# MCU_RF.net
KiCad netlist of a schematic drawn in Altium Designer
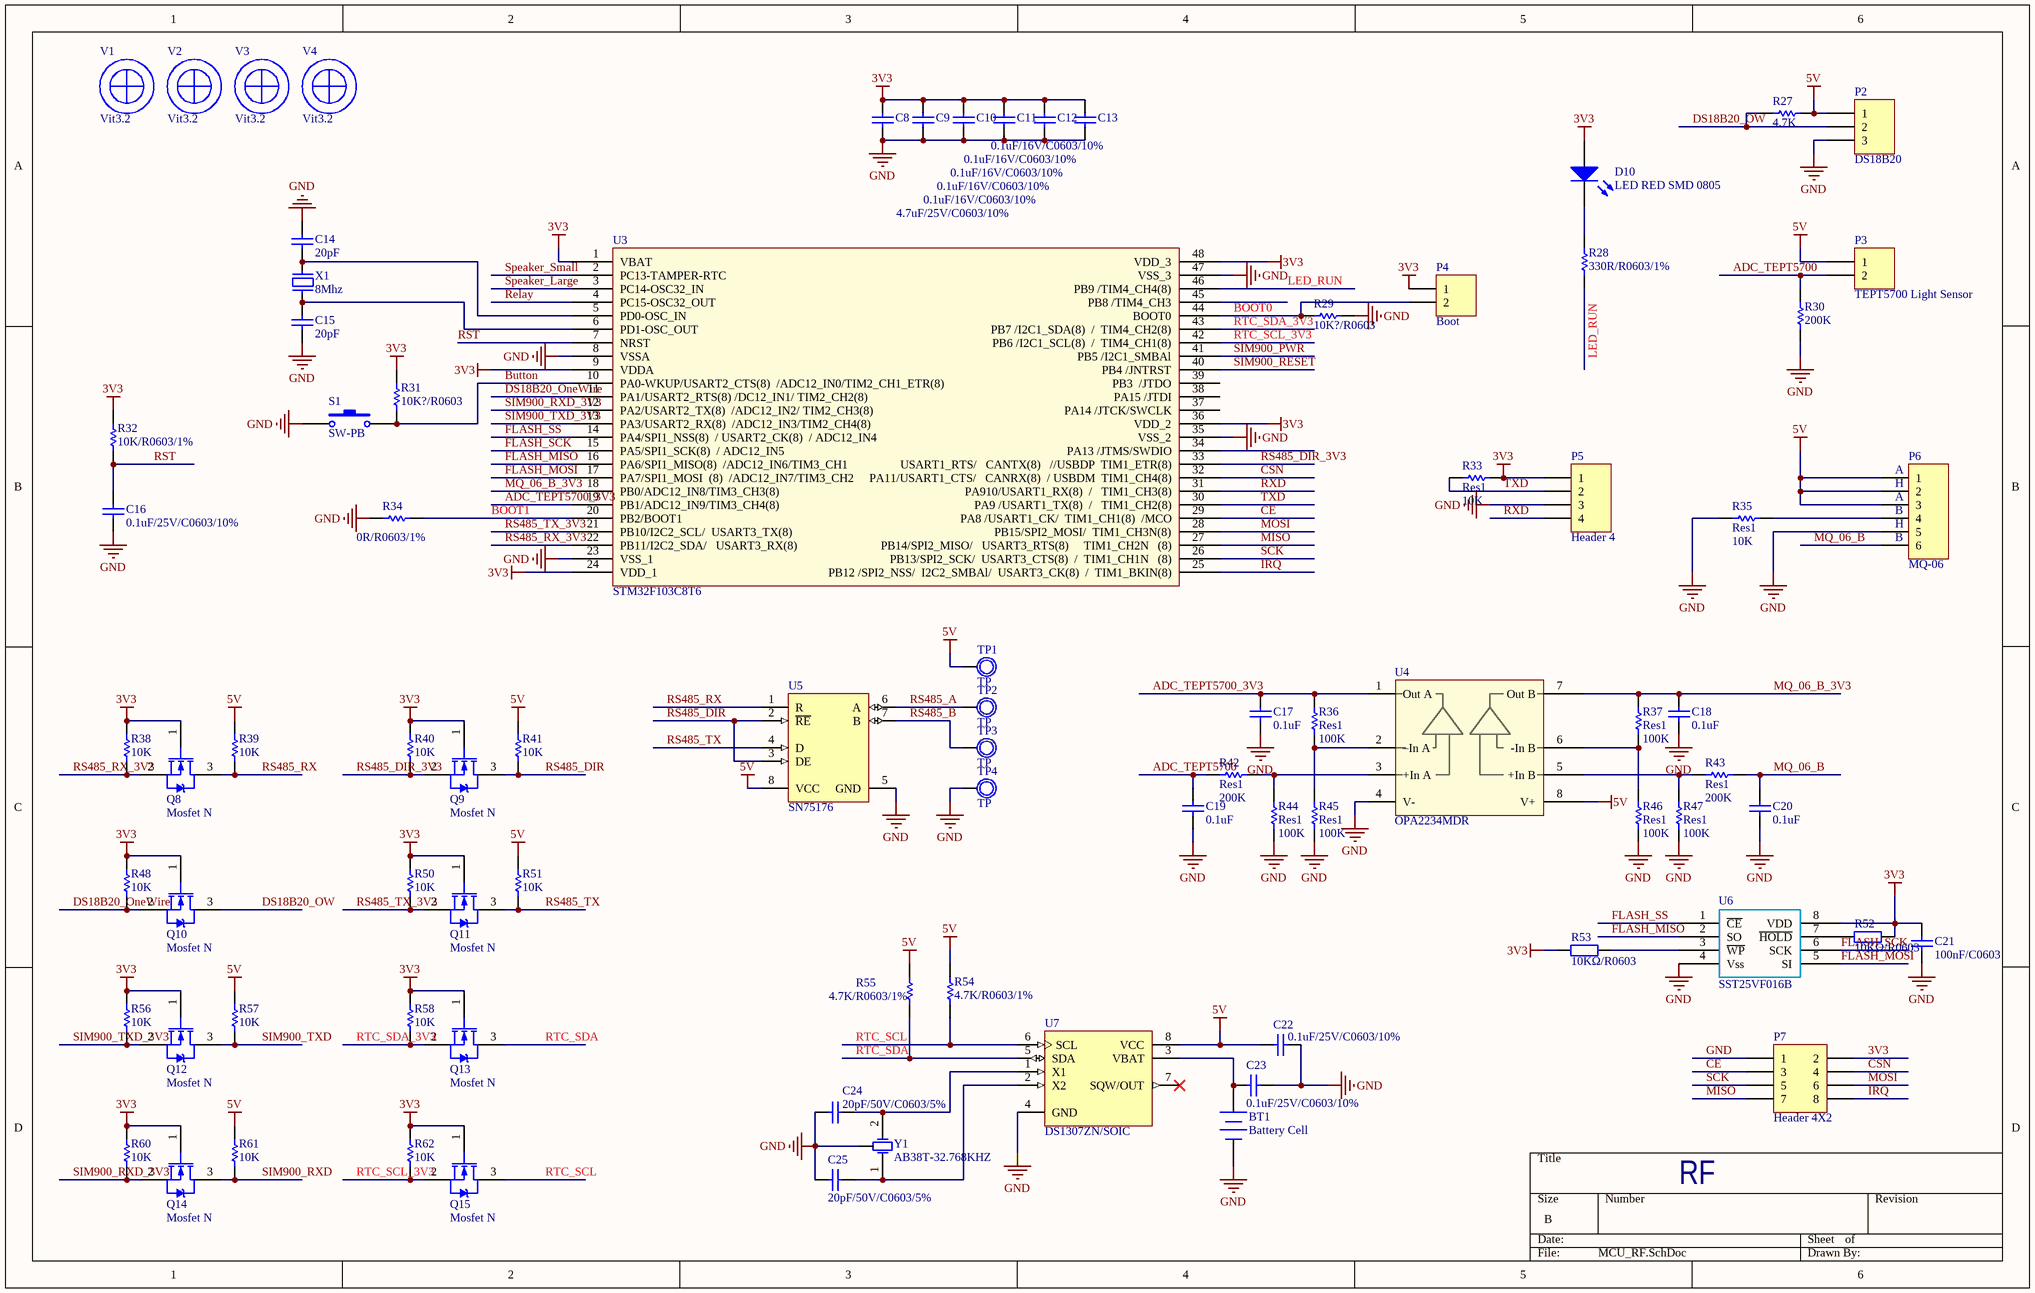
[diagram p0: MCU_RF.SchDoc]

(export (version "E")
  (design (tool "Eeschema 10.0.6"))
  (components
    (comp (ref "BT1")
      (value "Battery Cell")
      (footprint "Tuyens Library for Altium Designer:Battery CELL_HOLDER")
      (description "HOLDER COINCELL 2032 RETAINRCLIP")
      (fields
        (field (name "MANUFACTURER") "MPD (Memory Protection Devices)")
        (field (name "MANUFACTURER PART NUMBER") "BS-7")
      )
      (libsource (lib "Manh_Miscellaneous") (part "Battery Holder Cell 20mm"))
    )
    (comp (ref "C8")
      (value "4.7uF/25V/C0603/10%")
      (footprint "Tuyens Library for Altium Designer:C0603")
      (description "CAP CER 4.7UF 25V 10% X6S 0603")
      (fields
        (field (name "MANUFACTURER") "Murata Electronics North America")
        (field (name "MANUFACTURER PART NUMBER") "GRM188C81E475KE11D")
      )
      (libsource (lib "Manh_Capacitor") (part "4.7uF/25V/C0603/10%"))
    )
    (comp (ref "C9")
      (value "0.1uF/16V/C0603/10%")
      (footprint "Tuyens Library for Altium Designer:C0603")
      (description "CAP CER 0.1UF 16V 10% X7R 0603")
      (fields
        (field (name "MANUFACTURER") "Kemet")
        (field (name "MANUFACTURER PART NUMBER") "C0603C104K4RACTU")
      )
      (libsource (lib "Manh_Capacitor") (part "0.1uF/16V/C0603/10%"))
    )
    (comp (ref "C10")
      (value "0.1uF/16V/C0603/10%")
      (footprint "Tuyens Library for Altium Designer:C0603")
      (description "CAP CER 0.1UF 16V 10% X7R 0603")
      (fields
        (field (name "MANUFACTURER") "Kemet")
        (field (name "MANUFACTURER PART NUMBER") "C0603C104K4RACTU")
      )
      (libsource (lib "Manh_Capacitor") (part "0.1uF/16V/C0603/10%"))
    )
    (comp (ref "C11")
      (value "0.1uF/16V/C0603/10%")
      (footprint "Tuyens Library for Altium Designer:C0603")
      (description "CAP CER 0.1UF 16V 10% X7R 0603")
      (fields
        (field (name "MANUFACTURER") "Kemet")
        (field (name "MANUFACTURER PART NUMBER") "C0603C104K4RACTU")
      )
      (libsource (lib "Manh_Capacitor") (part "0.1uF/16V/C0603/10%"))
    )
    (comp (ref "C12")
      (value "0.1uF/16V/C0603/10%")
      (footprint "Tuyens Library for Altium Designer:C0603")
      (description "CAP CER 0.1UF 16V 10% X7R 0603")
      (fields
        (field (name "MANUFACTURER") "Kemet")
        (field (name "MANUFACTURER PART NUMBER") "C0603C104K4RACTU")
      )
      (libsource (lib "Manh_Capacitor") (part "0.1uF/16V/C0603/10%"))
    )
    (comp (ref "C13")
      (value "0.1uF/16V/C0603/10%")
      (footprint "Tuyens Library for Altium Designer:C0603")
      (description "CAP CER 0.1UF 16V 10% X7R 0603")
      (fields
        (field (name "MANUFACTURER") "Kemet")
        (field (name "MANUFACTURER PART NUMBER") "C0603C104K4RACTU")
      )
      (libsource (lib "Manh_Capacitor") (part "0.1uF/16V/C0603/10%"))
    )
    (comp (ref "C14")
      (value "20pF")
      (footprint "C0603")
      (description "Capacitor")
      (libsource (lib "Miscellaneous Devices") (part "Cap"))
    )
    (comp (ref "C15")
      (value "20pF")
      (footprint "C0603")
      (description "Capacitor")
      (libsource (lib "Miscellaneous Devices") (part "Cap"))
    )
    (comp (ref "C16")
      (value "0.1uF/25V/C0603/10%")
      (footprint "Tuyens Library for Altium Designer:C0603")
      (description "CAP CER 0.1UF 25V 10% X7R 0603")
      (fields
        (field (name "MANUFACTURER") "Murata Electronics North America")
        (field (name "MANUFACTURER PART NUMBER") "GRM188R71E104KA01D")
      )
      (libsource (lib "Manh_Capacitor") (part "0.1uF/25V/C0603/10%"))
    )
    (comp (ref "C17")
      (value "0.1uF")
      (footprint "Tuyens Library for Altium Designer:C0603")
      (description "CAP CER 0.1UF 25V 10% X7R 0603")
      (fields
        (field (name "MANUFACTURER") "Murata Electronics North America")
        (field (name "MANUFACTURER PART NUMBER") "GRM188R71E104KA01D")
      )
      (libsource (lib "Manh_Capacitor") (part "0.1uF/25V/C0603/10%"))
    )
    (comp (ref "C18")
      (value "0.1uF")
      (footprint "Tuyens Library for Altium Designer:C0603")
      (description "CAP CER 0.1UF 25V 10% X7R 0603")
      (fields
        (field (name "MANUFACTURER") "Murata Electronics North America")
        (field (name "MANUFACTURER PART NUMBER") "GRM188R71E104KA01D")
      )
      (libsource (lib "Manh_Capacitor") (part "0.1uF/25V/C0603/10%"))
    )
    (comp (ref "C19")
      (value "0.1uF")
      (footprint "Tuyens Library for Altium Designer:C0603")
      (description "CAP CER 0.1UF 25V 10% X7R 0603")
      (fields
        (field (name "MANUFACTURER") "Murata Electronics North America")
        (field (name "MANUFACTURER PART NUMBER") "GRM188R71E104KA01D")
      )
      (libsource (lib "Manh_Capacitor") (part "0.1uF/25V/C0603/10%"))
    )
    (comp (ref "C20")
      (value "0.1uF")
      (footprint "Tuyens Library for Altium Designer:C0603")
      (description "CAP CER 0.1UF 25V 10% X7R 0603")
      (fields
        (field (name "MANUFACTURER") "Murata Electronics North America")
        (field (name "MANUFACTURER PART NUMBER") "GRM188R71E104KA01D")
      )
      (libsource (lib "Manh_Capacitor") (part "0.1uF/25V/C0603/10%"))
    )
    (comp (ref "C21")
      (value "100nF/C0603")
      (footprint "c0603")
      (description "Capacitor")
      (fields (field (name "PUBLISHER") "Altium Limited"))
      (libsource (lib "Miscellaneous Devices") (part "Cap"))
    )
    (comp (ref "C22")
      (value "0.1uF/25V/C0603/10%")
      (footprint "Tuyens Library for Altium Designer:C0603")
      (description "CAP CER 0.1UF 25V 10% X7R 0603")
      (fields
        (field (name "MANUFACTURER") "Murata Electronics North America")
        (field (name "MANUFACTURER PART NUMBER") "GRM188R71E104KA01D")
      )
      (libsource (lib "Manh_Capacitor") (part "0.1uF/25V/C0603/10%"))
    )
    (comp (ref "C23")
      (value "0.1uF/25V/C0603/10%")
      (footprint "Tuyens Library for Altium Designer:C0603")
      (description "CAP CER 0.1UF 25V 10% X7R 0603")
      (fields
        (field (name "MANUFACTURER") "Murata Electronics North America")
        (field (name "MANUFACTURER PART NUMBER") "GRM188R71E104KA01D")
      )
      (libsource (lib "Manh_Capacitor") (part "0.1uF/25V/C0603/10%"))
    )
    (comp (ref "C24")
      (value "20pF/50V/C0603/5%")
      (footprint "Tuyens Library for Altium Designer:C0603")
      (description "CAP CER 20PF 50V 5% NP0 0603")
      (fields
        (field (name "MANUFACTURER") "Samsung Electro-Mechanics America, Inc.")
        (field (name "MANUFACTURER PART NUMBER") "CL10C200JB8NNNC")
      )
      (libsource (lib "Manh_Capacitor") (part "20pF/50V/C0603/5%"))
    )
    (comp (ref "C25")
      (value "20pF/50V/C0603/5%")
      (footprint "Tuyens Library for Altium Designer:C0603")
      (description "CAP CER 20PF 50V 5% NP0 0603")
      (fields
        (field (name "MANUFACTURER") "Samsung Electro-Mechanics America, Inc.")
        (field (name "MANUFACTURER PART NUMBER") "CL10C200JB8NNNC")
      )
      (libsource (lib "Manh_Capacitor") (part "20pF/50V/C0603/5%"))
    )
    (comp (ref "D10")
      (value "LED RED SMD 0805")
      (footprint "Tuyens Library for Altium Designer:led0805")
      (description "LED RED DIFFUSED 0805 SMD")
      (fields
        (field (name "MANUFACTURER") "OSRAM Opto Semiconductors Inc.")
        (field (name "MANUFACTURER PART NUMBER") "LH R974-LP-1")
      )
      (libsource (lib "Manh_LED") (part "LED RED SMD 0805"))
    )
    (comp (ref "P2")
      (value "DS18B20")
      (footprint "HDR1X3")
      (description "Header, 3-Pin")
      (fields (field (name "PUBLISHER") "Altium Limited"))
      (libsource (lib "Miscellaneous Connectors") (part "Header 3"))
    )
    (comp (ref "P3")
      (value "TEPT5700 Light Sensor")
      (footprint "LED-5-BLUE")
      (description "Header, 2-Pin")
      (fields (field (name "PUBLISHER") "Altium Limited"))
      (libsource (lib "Miscellaneous Connectors") (part "Header 2"))
    )
    (comp (ref "P4")
      (value "Boot")
      (footprint "HDR1X2")
      (description "Header, 2-Pin")
      (fields (field (name "PUBLISHER") "Altium Limited"))
      (libsource (lib "Miscellaneous Connectors") (part "Header 2"))
    )
    (comp (ref "P5")
      (value "Header 4")
      (footprint "HDR1X4")
      (description "Header, 4-Pin")
      (fields (field (name "PUBLISHER") "Altium Limited"))
      (libsource (lib "Miscellaneous Connectors") (part "Header 4"))
    )
    (comp (ref "P6")
      (value "MQ-06")
      (footprint "MQ-02")
      (description "Header, 6-Pin")
      (fields (field (name "PUBLISHER") "Altium Limited"))
      (libsource (lib "Miscellaneous Connectors") (part "Header 6"))
    )
    (comp (ref "P7")
      (value "Header 4X2")
      (footprint "HDR2X4")
      (description "Header, 4-Pin, Dual row")
      (fields (field (name "PUBLISHER") "Altium Limited"))
      (libsource (lib "Miscellaneous Connectors") (part "Header 4X2"))
    )
    (comp (ref "Q8")
      (value "Mosfet N")
      (footprint "SOT 23")
      (libsource (lib "Tuyens Library for Altium Designer") (part "Mosfet N"))
    )
    (comp (ref "Q9")
      (value "Mosfet N")
      (footprint "SOT 23")
      (libsource (lib "Tuyens Library for Altium Designer") (part "Mosfet N"))
    )
    (comp (ref "Q10")
      (value "Mosfet N")
      (footprint "SOT 23")
      (libsource (lib "Tuyens Library for Altium Designer") (part "Mosfet N"))
    )
    (comp (ref "Q11")
      (value "Mosfet N")
      (footprint "SOT 23")
      (libsource (lib "Tuyens Library for Altium Designer") (part "Mosfet N"))
    )
    (comp (ref "Q12")
      (value "Mosfet N")
      (footprint "SOT 23")
      (libsource (lib "Tuyens Library for Altium Designer") (part "Mosfet N"))
    )
    (comp (ref "Q13")
      (value "Mosfet N")
      (footprint "SOT 23")
      (libsource (lib "Tuyens Library for Altium Designer") (part "Mosfet N"))
    )
    (comp (ref "Q14")
      (value "Mosfet N")
      (footprint "SOT 23")
      (libsource (lib "Tuyens Library for Altium Designer") (part "Mosfet N"))
    )
    (comp (ref "Q15")
      (value "Mosfet N")
      (footprint "SOT 23")
      (libsource (lib "Tuyens Library for Altium Designer") (part "Mosfet N"))
    )
    (comp (ref "R27")
      (value "4.7K")
      (footprint "SM-RES-0805")
      (description "Resistor")
      (fields (field (name "Comment") "Res1") (field (name "PUBLISHER") "Altium Limited"))
      (libsource (lib "Miscellaneous Devices") (part "Res1"))
    )
    (comp (ref "R28")
      (value "330R/R0603/1%")
      (footprint "Tuyens Library for Altium Designer:R0603")
      (description "RES SMD 330 OHM 1% 1/10W 0603")
      (fields
        (field (name "MANUFACTURER") "Yageo")
        (field (name "MANUFACTURER PART NUMBER") "RC0603FR-07330RL")
      )
      (libsource (lib "Manh_Resistor") (part "330R/R0603/1%"))
    )
    (comp (ref "R29")
      (value "10K?/R0603")
      (footprint "R0603")
      (description "Resistor")
      (libsource (lib "Miscellaneous Devices") (part "Res1"))
    )
    (comp (ref "R30")
      (value "200K")
      (footprint "SM-RES-0805")
      (description "Resistor")
      (fields (field (name "Comment") "Res1") (field (name "PUBLISHER") "Altium Limited"))
      (libsource (lib "Miscellaneous Devices") (part "Res1"))
    )
    (comp (ref "R31")
      (value "10K?/R0603")
      (footprint "R0603")
      (description "Resistor")
      (libsource (lib "Miscellaneous Devices") (part "Res1"))
    )
    (comp (ref "R32")
      (value "10K/R0603/1%")
      (footprint "Tuyens Library for Altium Designer:R0603")
      (description "RES SMD 10M OHM 1% 1/10W 0603")
      (fields
        (field (name "MANUFACTURER") "Yageo")
        (field (name "MANUFACTURER PART NUMBER") "RC0603FR-0710ML")
      )
      (libsource (lib "Manh_Resistor") (part "10M/R0603/1%"))
    )
    (comp (ref "R33")
      (value "Res1")
      (footprint "R0603")
      (description "Resistor")
      (fields (field (name "ALTIUM_VALUE") "10K") (field (name "PUBLISHER") "Altium Limited"))
      (libsource (lib "Miscellaneous Devices") (part "Res1"))
    )
    (comp (ref "R34")
      (value "0R/R0603/1%")
      (footprint "Tuyens Library for Altium Designer:R0603")
      (description "RES SMD 0.01 OHM 1% 1/10W 0603")
      (fields
        (field (name "MANUFACTURER") "Yageo")
        (field (name "MANUFACTURER PART NUMBER") "RL0603FR-070R01L")
      )
      (libsource (lib "Manh_Resistor") (part "0R/R0603/1%"))
    )
    (comp (ref "R35")
      (value "Res1")
      (footprint "SM-RES-0805")
      (description "Resistor")
      (fields (field (name "ALTIUM_VALUE") "10K") (field (name "PUBLISHER") "Altium Limited"))
      (libsource (lib "Miscellaneous Devices") (part "Res1"))
    )
    (comp (ref "R36")
      (value "Res1")
      (footprint "R0603")
      (description "Resistor")
      (fields (field (name "ALTIUM_VALUE") "100K") (field (name "PUBLISHER") "Altium Limited"))
      (libsource (lib "Miscellaneous Devices") (part "Res1"))
    )
    (comp (ref "R37")
      (value "Res1")
      (footprint "R0603")
      (description "Resistor")
      (fields (field (name "ALTIUM_VALUE") "100K") (field (name "PUBLISHER") "Altium Limited"))
      (libsource (lib "Miscellaneous Devices") (part "Res1"))
    )
    (comp (ref "R38")
      (value "10K")
      (footprint "Tuyens Library for Altium Designer:R0603")
      (description "RES SMD 4.7K OHM 1% 1/10W 0603")
      (fields
        (field (name "MANUFACTURER") "Yageo")
        (field (name "MANUFACTURER PART NUMBER") "RC0603FR-074K7L")
      )
      (libsource (lib "Manh_Resistor") (part "4.7K/R0603/1%"))
    )
    (comp (ref "R39")
      (value "10K")
      (footprint "Tuyens Library for Altium Designer:R0603")
      (description "RES SMD 4.7K OHM 1% 1/10W 0603")
      (fields
        (field (name "MANUFACTURER") "Yageo")
        (field (name "MANUFACTURER PART NUMBER") "RC0603FR-074K7L")
      )
      (libsource (lib "Manh_Resistor") (part "4.7K/R0603/1%"))
    )
    (comp (ref "R40")
      (value "10K")
      (footprint "Tuyens Library for Altium Designer:R0603")
      (description "RES SMD 4.7K OHM 1% 1/10W 0603")
      (fields
        (field (name "MANUFACTURER") "Yageo")
        (field (name "MANUFACTURER PART NUMBER") "RC0603FR-074K7L")
      )
      (libsource (lib "Manh_Resistor") (part "4.7K/R0603/1%"))
    )
    (comp (ref "R41")
      (value "10K")
      (footprint "Tuyens Library for Altium Designer:R0603")
      (description "RES SMD 4.7K OHM 1% 1/10W 0603")
      (fields
        (field (name "MANUFACTURER") "Yageo")
        (field (name "MANUFACTURER PART NUMBER") "RC0603FR-074K7L")
      )
      (libsource (lib "Manh_Resistor") (part "4.7K/R0603/1%"))
    )
    (comp (ref "R42")
      (value "Res1")
      (footprint "R0603")
      (description "Resistor")
      (fields (field (name "ALTIUM_VALUE") "200K") (field (name "PUBLISHER") "Altium Limited"))
      (libsource (lib "Miscellaneous Devices") (part "Res1"))
    )
    (comp (ref "R43")
      (value "Res1")
      (footprint "R0603")
      (description "Resistor")
      (fields (field (name "ALTIUM_VALUE") "200K") (field (name "PUBLISHER") "Altium Limited"))
      (libsource (lib "Miscellaneous Devices") (part "Res1"))
    )
    (comp (ref "R44")
      (value "Res1")
      (footprint "R0603")
      (description "Resistor")
      (fields (field (name "ALTIUM_VALUE") "100K") (field (name "PUBLISHER") "Altium Limited"))
      (libsource (lib "Miscellaneous Devices") (part "Res1"))
    )
    (comp (ref "R45")
      (value "Res1")
      (footprint "R0603")
      (description "Resistor")
      (fields (field (name "ALTIUM_VALUE") "100K") (field (name "PUBLISHER") "Altium Limited"))
      (libsource (lib "Miscellaneous Devices") (part "Res1"))
    )
    (comp (ref "R46")
      (value "Res1")
      (footprint "R0603")
      (description "Resistor")
      (fields (field (name "ALTIUM_VALUE") "100K") (field (name "PUBLISHER") "Altium Limited"))
      (libsource (lib "Miscellaneous Devices") (part "Res1"))
    )
    (comp (ref "R47")
      (value "Res1")
      (footprint "R0603")
      (description "Resistor")
      (fields (field (name "ALTIUM_VALUE") "100K") (field (name "PUBLISHER") "Altium Limited"))
      (libsource (lib "Miscellaneous Devices") (part "Res1"))
    )
    (comp (ref "R48")
      (value "10K")
      (footprint "Tuyens Library for Altium Designer:R0603")
      (description "RES SMD 4.7K OHM 1% 1/10W 0603")
      (fields
        (field (name "MANUFACTURER") "Yageo")
        (field (name "MANUFACTURER PART NUMBER") "RC0603FR-074K7L")
      )
      (libsource (lib "Manh_Resistor") (part "4.7K/R0603/1%"))
    )
    (comp (ref "R50")
      (value "10K")
      (footprint "Tuyens Library for Altium Designer:R0603")
      (description "RES SMD 4.7K OHM 1% 1/10W 0603")
      (fields
        (field (name "MANUFACTURER") "Yageo")
        (field (name "MANUFACTURER PART NUMBER") "RC0603FR-074K7L")
      )
      (libsource (lib "Manh_Resistor") (part "4.7K/R0603/1%"))
    )
    (comp (ref "R51")
      (value "10K")
      (footprint "Tuyens Library for Altium Designer:R0603")
      (description "RES SMD 4.7K OHM 1% 1/10W 0603")
      (fields
        (field (name "MANUFACTURER") "Yageo")
        (field (name "MANUFACTURER PART NUMBER") "RC0603FR-074K7L")
      )
      (libsource (lib "Manh_Resistor") (part "4.7K/R0603/1%"))
    )
    (comp (ref "R52")
      (value "10KΩ/R0603")
      (footprint "r0603")
      (description "Resistor")
      (libsource (lib "Miscellaneous Devices") (part "Res2"))
    )
    (comp (ref "R53")
      (value "10KΩ/R0603")
      (footprint "r0603")
      (description "Resistor")
      (libsource (lib "Miscellaneous Devices") (part "Res2"))
    )
    (comp (ref "R54")
      (value "4.7K/R0603/1%")
      (footprint "Tuyens Library for Altium Designer:R0603")
      (description "RES SMD 4.7K OHM 1% 1/10W 0603")
      (fields
        (field (name "MANUFACTURER") "Yageo")
        (field (name "MANUFACTURER PART NUMBER") "RC0603FR-074K7L")
      )
      (libsource (lib "Manh_Resistor") (part "4.7K/R0603/1%"))
    )
    (comp (ref "R55")
      (value "4.7K/R0603/1%")
      (footprint "Tuyens Library for Altium Designer:R0603")
      (description "RES SMD 4.7K OHM 1% 1/10W 0603")
      (fields
        (field (name "MANUFACTURER") "Yageo")
        (field (name "MANUFACTURER PART NUMBER") "RC0603FR-074K7L")
      )
      (libsource (lib "Manh_Resistor") (part "4.7K/R0603/1%"))
    )
    (comp (ref "R56")
      (value "10K")
      (footprint "Tuyens Library for Altium Designer:R0603")
      (description "RES SMD 4.7K OHM 1% 1/10W 0603")
      (fields
        (field (name "MANUFACTURER") "Yageo")
        (field (name "MANUFACTURER PART NUMBER") "RC0603FR-074K7L")
      )
      (libsource (lib "Manh_Resistor") (part "4.7K/R0603/1%"))
    )
    (comp (ref "R57")
      (value "10K")
      (footprint "Tuyens Library for Altium Designer:R0603")
      (description "RES SMD 4.7K OHM 1% 1/10W 0603")
      (fields
        (field (name "MANUFACTURER") "Yageo")
        (field (name "MANUFACTURER PART NUMBER") "RC0603FR-074K7L")
      )
      (libsource (lib "Manh_Resistor") (part "4.7K/R0603/1%"))
    )
    (comp (ref "R58")
      (value "10K")
      (footprint "Tuyens Library for Altium Designer:R0603")
      (description "RES SMD 4.7K OHM 1% 1/10W 0603")
      (fields
        (field (name "MANUFACTURER") "Yageo")
        (field (name "MANUFACTURER PART NUMBER") "RC0603FR-074K7L")
      )
      (libsource (lib "Manh_Resistor") (part "4.7K/R0603/1%"))
    )
    (comp (ref "R60")
      (value "10K")
      (footprint "Tuyens Library for Altium Designer:R0603")
      (description "RES SMD 4.7K OHM 1% 1/10W 0603")
      (fields
        (field (name "MANUFACTURER") "Yageo")
        (field (name "MANUFACTURER PART NUMBER") "RC0603FR-074K7L")
      )
      (libsource (lib "Manh_Resistor") (part "4.7K/R0603/1%"))
    )
    (comp (ref "R61")
      (value "10K")
      (footprint "Tuyens Library for Altium Designer:R0603")
      (description "RES SMD 4.7K OHM 1% 1/10W 0603")
      (fields
        (field (name "MANUFACTURER") "Yageo")
        (field (name "MANUFACTURER PART NUMBER") "RC0603FR-074K7L")
      )
      (libsource (lib "Manh_Resistor") (part "4.7K/R0603/1%"))
    )
    (comp (ref "R62")
      (value "10K")
      (footprint "Tuyens Library for Altium Designer:R0603")
      (description "RES SMD 4.7K OHM 1% 1/10W 0603")
      (fields
        (field (name "MANUFACTURER") "Yageo")
        (field (name "MANUFACTURER PART NUMBER") "RC0603FR-074K7L")
      )
      (libsource (lib "Manh_Resistor") (part "4.7K/R0603/1%"))
    )
    (comp (ref "S1")
      (value "SW-PB")
      (footprint "Button-2pin")
      (description "Switch")
      (fields (field (name "PUBLISHER") "Altium Limited"))
      (libsource (lib "Tuyens Library for Altium Designer") (part "SW-PB"))
    )
    (comp (ref "TP1")
      (value "TP")
      (footprint "TP1")
      (description "Test Point")
      (libsource (lib "syhaunguyen") (part "TP1"))
    )
    (comp (ref "TP2")
      (value "TP")
      (footprint "TP1")
      (description "Test Point")
      (libsource (lib "syhaunguyen") (part "TP1"))
    )
    (comp (ref "TP3")
      (value "TP")
      (footprint "TP1")
      (description "Test Point")
      (libsource (lib "syhaunguyen") (part "TP1"))
    )
    (comp (ref "TP4")
      (value "TP")
      (footprint "TP1")
      (description "Test Point")
      (libsource (lib "syhaunguyen") (part "TP1"))
    )
    (comp (ref "U3")
      (value "STM32F103C8T6")
      (footprint "ST_TSQFP50P910X910X160-48N")
      (libsource (lib "Tuyens Library for Altium Designer") (part "STM32F103C8T6"))
    )
    (comp (ref "U4")
      (value "OPA2234MDR")
      (footprint "SOP 8Pin")
      (description "LOW-POWER, PRECISION  SINGLE-SUPPLY OPERATIONAL AMPLIFIERS")
      (libsource (lib "Tuyens Library for Altium Designer") (part "OPA2234M"))
    )
    (comp (ref "U5")
      (value "SN75176")
      (footprint "SOP127P600X175-8N")
      (description "RS485 Interface")
      (libsource (lib "tqk") (part "SN75176_RS485"))
    )
    (comp (ref "U6")
      (value "SST25VF016B")
      (footprint "SOIC8")
      (libsource (lib "Tuyen's Library for Altium Designer") (part "SST25VF016B"))
    )
    (comp (ref "U7")
      (value "DS1307ZN/SOIC")
      (footprint "Tuyens Library for Altium Designer:SOIC-8")
      (description "IC RTC CLK/CALENDAR I2C 8-SOIC")
      (fields
        (field (name "MANUFACTURER") "Maxim Integrated")
        (field (name "MANUFACTURER PART NUMBER") "DS1307ZN+T&R")
      )
      (libsource (lib "Manh_MCU") (part "DS1307ZN+T&R"))
    )
    (comp (ref "V1")
      (value "Vit3.2")
      (footprint "Vit3.2")
      (libsource (lib "Tuyens Library for Altium Designer") (part "Vit3.2"))
    )
    (comp (ref "V2")
      (value "Vit3.2")
      (footprint "Vit3.2")
      (libsource (lib "Tuyens Library for Altium Designer") (part "Vit3.2"))
    )
    (comp (ref "V3")
      (value "Vit3.2")
      (footprint "Vit3.2")
      (libsource (lib "Tuyens Library for Altium Designer") (part "Vit3.2"))
    )
    (comp (ref "V4")
      (value "Vit3.2")
      (footprint "Vit3.2")
      (libsource (lib "Tuyens Library for Altium Designer") (part "Vit3.2"))
    )
    (comp (ref "X1")
      (value "8Mhz")
      (footprint "XT2")
      (description "Crystal For all Crystal 2pin.")
      (libsource (lib "syhaunguyen") (part "XT2"))
    )
    (comp (ref "Y1")
      (value "AB38T-32.768KHZ")
      (footprint "Tuyens Library for Altium Designer:ZTA - 38k")
      (description "CRYSTAL 32.7680KHZ 12.5PF T/H")
      (fields (field (name "MANUFACTURER") "Abracon LLC"))
      (libsource (lib "Manh_Crystal") (part "AB38T-32.768KHZ"))
    )
  )
  (nets
    (net (code "1") (name "/ADC_TEPT5700") (class "Default")
      (node (ref "C19") (pin "1") (pinfunction "1_1") (pintype "passive"))
      (node (ref "P3") (pin "2") (pinfunction "2_2") (pintype "passive"))
      (node (ref "R30") (pin "2") (pinfunction "2_2") (pintype "passive"))
      (node (ref "R42") (pin "1") (pinfunction "1_1") (pintype "passive"))
    )
    (net (code "2") (name "/ADC_TEPT5700_3V3") (class "Default")
      (node (ref "C17") (pin "1") (pinfunction "1_1") (pintype "passive"))
      (node (ref "R36") (pin "2") (pinfunction "2_2") (pintype "passive"))
      (node (ref "U3") (pin "19") (pinfunction "PB1/ADC12_IN9/TIM3_CH4(8)_19") (pintype "passive"))
      (node (ref "U4") (pin "1") (pinfunction "Out_A_1") (pintype "passive"))
    )
    (net (code "3") (name "/BOOT0") (class "Default")
      (node (ref "P4") (pin "2") (pinfunction "2_2") (pintype "passive"))
      (node (ref "R29") (pin "2") (pinfunction "2_2") (pintype "passive"))
      (node (ref "U3") (pin "44") (pinfunction "BOOT0_44") (pintype "passive"))
    )
    (net (code "4") (name "/BOOT1") (class "Default")
      (node (ref "R34") (pin "2") (pinfunction "2_2") (pintype "passive"))
      (node (ref "U3") (pin "20") (pinfunction "PB2/BOOT1_20") (pintype "passive"))
    )
    (net (code "5") (name "/Button") (class "Default")
      (node (ref "R31") (pin "2") (pinfunction "2_2") (pintype "passive"))
      (node (ref "S1") (pin "2") (pinfunction "2_2") (pintype "passive"))
      (node (ref "U3") (pin "10") (pinfunction "PA0-WKUP/USART2_CTS(8)__/ADC12_IN0/TIM2_CH1_ETR(8)_10") (pintype "passive"))
    )
    (net (code "6") (name "/CE") (class "Default")
      (node (ref "P7") (pin "3") (pinfunction "3_3") (pintype "passive"))
      (node (ref "U3") (pin "29") (pinfunction "PA8_/USART1_CK/__TIM1_CH1(8)__/MCO_29") (pintype "passive"))
    )
    (net (code "7") (name "/CSN") (class "Default")
      (node (ref "P7") (pin "4") (pinfunction "4_4") (pintype "passive"))
      (node (ref "U3") (pin "32") (pinfunction "PA11/USART1_CTS/___CANRX(8)__/_USBDM__TIM1_CH4(8)_32") (pintype "passive"))
    )
    (net (code "8") (name "/DS18B20_OW") (class "Default")
      (node (ref "P2") (pin "2") (pinfunction "2_2") (pintype "passive"))
      (node (ref "Q10") (pin "3") (pinfunction "D_3") (pintype "passive"))
      (node (ref "R27") (pin "2") (pinfunction "2_2") (pintype "passive"))
    )
    (net (code "9") (name "/DS18B20_OneWire") (class "Default")
      (node (ref "Q10") (pin "2") (pinfunction "S_2") (pintype "passive"))
      (node (ref "R48") (pin "2") (pinfunction "2_2") (pintype "passive"))
      (node (ref "U3") (pin "11") (pinfunction "PA1/USART2_RTS(8)_/DC12_IN1/_TIM2_CH2(8)_11") (pintype "passive"))
    )
    (net (code "10") (name "/FLASH_MISO") (class "Default")
      (node (ref "U3") (pin "16") (pinfunction "PA6/SPI1_MISO(8)__/ADC12_IN6/TIM3_CH1_16") (pintype "passive"))
      (node (ref "U6") (pin "2") (pinfunction "SO_2") (pintype "passive"))
    )
    (net (code "11") (name "/FLASH_MOSI") (class "Default")
      (node (ref "U3") (pin "17") (pinfunction "PA7/SPI1_MOSI__(8)__/ADC12_IN7/TIM3_CH2_17") (pintype "passive"))
      (node (ref "U6") (pin "5") (pinfunction "SI_5") (pintype "passive"))
    )
    (net (code "12") (name "/FLASH_SCK") (class "Default")
      (node (ref "U3") (pin "15") (pinfunction "PA5/SPI1_SCK(8)__/_ADC12_IN5_15") (pintype "passive"))
      (node (ref "U6") (pin "6") (pinfunction "SCK_6") (pintype "passive"))
    )
    (net (code "13") (name "/FLASH_SS") (class "Default")
      (node (ref "U3") (pin "14") (pinfunction "PA4/SPI1_NSS(8)__/_USART2_CK(8)__/_ADC12_IN4_14") (pintype "passive"))
      (node (ref "U6") (pin "1") (pinfunction "~{CE}_1") (pintype "passive"))
    )
    (net (code "14") (name "/IRQ") (class "Default")
      (node (ref "P7") (pin "8") (pinfunction "8_8") (pintype "passive"))
      (node (ref "U3") (pin "25") (pinfunction "PB12_/SPI2_NSS/__I2C2_SMBAl/__USART3_CK(8)__/__TIM1_BKIN(8)_25") (pintype "passive"))
    )
    (net (code "15") (name "/LED_RUN") (class "Default")
      (node (ref "R28") (pin "2") (pinfunction "2_2") (pintype "passive"))
      (node (ref "U3") (pin "46") (pinfunction "PB9_/TIM4_CH4(8)_46") (pintype "passive"))
    )
    (net (code "16") (name "/MISO") (class "Default")
      (node (ref "P7") (pin "7") (pinfunction "7_7") (pintype "passive"))
      (node (ref "U3") (pin "27") (pinfunction "PB14/SPI2_MISO/___USART3_RTS(8)_____TIM1_CH2N___(8)_27") (pintype "passive"))
    )
    (net (code "17") (name "/MOSI") (class "Default")
      (node (ref "P7") (pin "6") (pinfunction "6_6") (pintype "passive"))
      (node (ref "U3") (pin "28") (pinfunction "PB15/SPI2_MOSI/__TIM1_CH3N(8)_28") (pintype "passive"))
    )
    (net (code "18") (name "/MQ_06_B") (class "Default")
      (node (ref "C20") (pin "1") (pinfunction "1_1") (pintype "passive"))
      (node (ref "P6") (pin "6") (pinfunction "6_6") (pintype "passive"))
      (node (ref "R43") (pin "2") (pinfunction "2_2") (pintype "passive"))
    )
    (net (code "19") (name "/MQ_06_B_3V3") (class "Default")
      (node (ref "C18") (pin "1") (pinfunction "1_1") (pintype "passive"))
      (node (ref "R37") (pin "2") (pinfunction "2_2") (pintype "passive"))
      (node (ref "U3") (pin "18") (pinfunction "PB0/ADC12_IN8/TIM3_CH3(8)_18") (pintype "passive"))
      (node (ref "U4") (pin "7") (pinfunction "Out_B_7") (pintype "passive"))
    )
    (net (code "20") (name "/RS485_A") (class "Default")
      (node (ref "TP2") (pin "1") (pinfunction "1_1") (pintype "passive"))
      (node (ref "U5") (pin "6") (pinfunction "A_6") (pintype "bidirectional"))
    )
    (net (code "21") (name "/RS485_B") (class "Default")
      (node (ref "TP3") (pin "1") (pinfunction "1_1") (pintype "passive"))
      (node (ref "U5") (pin "7") (pinfunction "B_7") (pintype "bidirectional"))
    )
    (net (code "22") (name "/RS485_DIR") (class "Default")
      (node (ref "Q9") (pin "3") (pinfunction "D_3") (pintype "passive"))
      (node (ref "R41") (pin "2") (pinfunction "2_2") (pintype "passive"))
      (node (ref "U5") (pin "2") (pinfunction "~{RE}_2") (pintype "input"))
      (node (ref "U5") (pin "3") (pinfunction "DE_3") (pintype "input"))
    )
    (net (code "23") (name "/RS485_DIR_3V3") (class "Default")
      (node (ref "Q9") (pin "2") (pinfunction "S_2") (pintype "passive"))
      (node (ref "R40") (pin "2") (pinfunction "2_2") (pintype "passive"))
      (node (ref "U3") (pin "33") (pinfunction "USART1_RTS/___CANTX(8)___//USBDP__TIM1_ETR(8)_33") (pintype "passive"))
    )
    (net (code "24") (name "/RS485_RX") (class "Default")
      (node (ref "Q8") (pin "3") (pinfunction "D_3") (pintype "passive"))
      (node (ref "R39") (pin "2") (pinfunction "2_2") (pintype "passive"))
      (node (ref "U5") (pin "1") (pinfunction "R_1") (pintype "tri_state"))
    )
    (net (code "25") (name "/RS485_RX_3V3") (class "Default")
      (node (ref "Q8") (pin "2") (pinfunction "S_2") (pintype "passive"))
      (node (ref "R38") (pin "2") (pinfunction "2_2") (pintype "passive"))
      (node (ref "U3") (pin "22") (pinfunction "PB11/I2C2_SDA/___USART3_RX(8)_22") (pintype "passive"))
    )
    (net (code "26") (name "/RS485_TX") (class "Default")
      (node (ref "Q11") (pin "3") (pinfunction "D_3") (pintype "passive"))
      (node (ref "R51") (pin "2") (pinfunction "2_2") (pintype "passive"))
      (node (ref "U5") (pin "4") (pinfunction "D_4") (pintype "input"))
    )
    (net (code "27") (name "/RS485_TX_3V3") (class "Default")
      (node (ref "Q11") (pin "2") (pinfunction "S_2") (pintype "passive"))
      (node (ref "R50") (pin "2") (pinfunction "2_2") (pintype "passive"))
      (node (ref "U3") (pin "21") (pinfunction "PB10/I2C2_SCL/__USART3_TX(8)_21") (pintype "passive"))
    )
    (net (code "28") (name "/RST") (class "Default")
      (node (ref "C16") (pin "2") (pinfunction "2_2") (pintype "passive"))
      (node (ref "R32") (pin "1") (pinfunction "1_1") (pintype "passive"))
      (node (ref "U3") (pin "7") (pinfunction "NRST_7") (pintype "passive"))
    )
    (net (code "29") (name "/RTC_SCL") (class "Default")
      (node (ref "Q15") (pin "3") (pinfunction "D_3") (pintype "passive"))
      (node (ref "R54") (pin "1") (pinfunction "1_1") (pintype "passive"))
      (node (ref "U7") (pin "6") (pinfunction "SCL_6") (pintype "input"))
    )
    (net (code "30") (name "/RTC_SCL_3V3") (class "Default")
      (node (ref "Q15") (pin "2") (pinfunction "S_2") (pintype "passive"))
      (node (ref "R62") (pin "2") (pinfunction "2_2") (pintype "passive"))
      (node (ref "U3") (pin "42") (pinfunction "PB6_/I2C1_SCL(8)__/__TIM4_CH1(8)_42") (pintype "passive"))
    )
    (net (code "31") (name "/RTC_SDA") (class "Default")
      (node (ref "Q13") (pin "3") (pinfunction "D_3") (pintype "passive"))
      (node (ref "R55") (pin "1") (pinfunction "1_1") (pintype "passive"))
      (node (ref "U7") (pin "5") (pinfunction "SDA_5") (pintype "bidirectional"))
    )
    (net (code "32") (name "/RTC_SDA_3V3") (class "Default")
      (node (ref "Q13") (pin "2") (pinfunction "S_2") (pintype "passive"))
      (node (ref "R58") (pin "2") (pinfunction "2_2") (pintype "passive"))
      (node (ref "U3") (pin "43") (pinfunction "PB7_/I2C1_SDA(8)__/__TIM4_CH2(8)_43") (pintype "passive"))
    )
    (net (code "33") (name "/RXD") (class "Default")
      (node (ref "P5") (pin "4") (pinfunction "4_4") (pintype "passive"))
      (node (ref "U3") (pin "31") (pinfunction "PA910/USART1_RX(8)__/___TIM1_CH3(8)_31") (pintype "passive"))
    )
    (net (code "34") (name "/Relay") (class "Default")
      (node (ref "U3") (pin "4") (pinfunction "PC15-OSC32_OUT_4") (pintype "passive"))
    )
    (net (code "35") (name "/SCK") (class "Default")
      (node (ref "P7") (pin "5") (pinfunction "5_5") (pintype "passive"))
      (node (ref "U3") (pin "26") (pinfunction "PB13/SPI2_SCK/__USART3_CTS(8)__/__TIM1_CH1N___(8)_26") (pintype "passive"))
    )
    (net (code "36") (name "/SIM900_PWR") (class "Default")
      (node (ref "U3") (pin "41") (pinfunction "PB5_/I2C1_SMBAl_41") (pintype "passive"))
    )
    (net (code "37") (name "/SIM900_RESET") (class "Default")
      (node (ref "U3") (pin "40") (pinfunction "PB4_/JNTRST_40") (pintype "passive"))
    )
    (net (code "38") (name "/SIM900_RXD") (class "Default")
      (node (ref "Q14") (pin "3") (pinfunction "D_3") (pintype "passive"))
      (node (ref "R61") (pin "2") (pinfunction "2_2") (pintype "passive"))
    )
    (net (code "39") (name "/SIM900_RXD_3V3") (class "Default")
      (node (ref "Q14") (pin "2") (pinfunction "S_2") (pintype "passive"))
      (node (ref "R60") (pin "2") (pinfunction "2_2") (pintype "passive"))
      (node (ref "U3") (pin "12") (pinfunction "PA2/USART2_TX(8)__/ADC12_IN2/_TIM2_CH3(8)_12") (pintype "passive"))
    )
    (net (code "40") (name "/SIM900_TXD") (class "Default")
      (node (ref "Q12") (pin "3") (pinfunction "D_3") (pintype "passive"))
      (node (ref "R57") (pin "2") (pinfunction "2_2") (pintype "passive"))
    )
    (net (code "41") (name "/SIM900_TXD_3V3") (class "Default")
      (node (ref "Q12") (pin "2") (pinfunction "S_2") (pintype "passive"))
      (node (ref "R56") (pin "2") (pinfunction "2_2") (pintype "passive"))
      (node (ref "U3") (pin "13") (pinfunction "PA3/USART2_RX(8)__/ADC12_IN3/TIM2_CH4(8)_13") (pintype "passive"))
    )
    (net (code "42") (name "/Speaker_Large") (class "Default")
      (node (ref "U3") (pin "3") (pinfunction "PC14-OSC32_IN_3") (pintype "passive"))
    )
    (net (code "43") (name "/Speaker_Small") (class "Default")
      (node (ref "U3") (pin "2") (pinfunction "PC13-TAMPER-RTC_2") (pintype "passive"))
    )
    (net (code "44") (name "/TXD") (class "Default")
      (node (ref "P5") (pin "2") (pinfunction "2_2") (pintype "passive"))
      (node (ref "R33") (pin "1") (pinfunction "1_1") (pintype "passive"))
      (node (ref "U3") (pin "30") (pinfunction "PA9_/USART1_TX(8)__/___TIM1_CH2(8)_30") (pintype "passive"))
    )
    (net (code "45") (name "3V3") (class "Default")
      (node (ref "C10") (pin "2") (pinfunction "2_2") (pintype "passive"))
      (node (ref "C11") (pin "2") (pinfunction "2_2") (pintype "passive"))
      (node (ref "C12") (pin "2") (pinfunction "2_2") (pintype "passive"))
      (node (ref "C13") (pin "2") (pinfunction "2_2") (pintype "passive"))
      (node (ref "C21") (pin "2") (pinfunction "2_2") (pintype "passive"))
      (node (ref "C8") (pin "2") (pinfunction "2_2") (pintype "passive"))
      (node (ref "C9") (pin "2") (pinfunction "2_2") (pintype "passive"))
      (node (ref "D10") (pin "1") (pinfunction "A_1") (pintype "passive"))
      (node (ref "P4") (pin "1") (pinfunction "1_1") (pintype "passive"))
      (node (ref "P5") (pin "1") (pinfunction "1_1") (pintype "passive"))
      (node (ref "P7") (pin "2") (pinfunction "2_2") (pintype "passive"))
      (node (ref "Q10") (pin "1") (pinfunction "G_1") (pintype "passive"))
      (node (ref "Q11") (pin "1") (pinfunction "G_1") (pintype "passive"))
      (node (ref "Q12") (pin "1") (pinfunction "G_1") (pintype "passive"))
      (node (ref "Q13") (pin "1") (pinfunction "G_1") (pintype "passive"))
      (node (ref "Q14") (pin "1") (pinfunction "G_1") (pintype "passive"))
      (node (ref "Q15") (pin "1") (pinfunction "G_1") (pintype "passive"))
      (node (ref "Q8") (pin "1") (pinfunction "G_1") (pintype "passive"))
      (node (ref "Q9") (pin "1") (pinfunction "G_1") (pintype "passive"))
      (node (ref "R31") (pin "1") (pinfunction "1_1") (pintype "passive"))
      (node (ref "R32") (pin "2") (pinfunction "2_2") (pintype "passive"))
      (node (ref "R33") (pin "2") (pinfunction "2_2") (pintype "passive"))
      (node (ref "R38") (pin "1") (pinfunction "1_1") (pintype "passive"))
      (node (ref "R40") (pin "1") (pinfunction "1_1") (pintype "passive"))
      (node (ref "R48") (pin "1") (pinfunction "1_1") (pintype "passive"))
      (node (ref "R50") (pin "1") (pinfunction "1_1") (pintype "passive"))
      (node (ref "R52") (pin "2") (pinfunction "2_2") (pintype "passive"))
      (node (ref "R53") (pin "1") (pinfunction "1_1") (pintype "passive"))
      (node (ref "R56") (pin "1") (pinfunction "1_1") (pintype "passive"))
      (node (ref "R58") (pin "1") (pinfunction "1_1") (pintype "passive"))
      (node (ref "R60") (pin "1") (pinfunction "1_1") (pintype "passive"))
      (node (ref "R62") (pin "1") (pinfunction "1_1") (pintype "passive"))
      (node (ref "U3") (pin "1") (pinfunction "VBAT_1") (pintype "passive"))
      (node (ref "U3") (pin "24") (pinfunction "VDD_1_24") (pintype "passive"))
      (node (ref "U3") (pin "36") (pinfunction "VDD_2_36") (pintype "passive"))
      (node (ref "U3") (pin "48") (pinfunction "VDD_3_48") (pintype "passive"))
      (node (ref "U3") (pin "9") (pinfunction "VDDA_9") (pintype "passive"))
      (node (ref "U6") (pin "8") (pinfunction "VDD_8") (pintype "passive"))
    )
    (net (code "46") (name "5V") (class "Default")
      (node (ref "C22") (pin "2") (pinfunction "2_2") (pintype "passive"))
      (node (ref "P2") (pin "1") (pinfunction "1_1") (pintype "passive"))
      (node (ref "P3") (pin "1") (pinfunction "1_1") (pintype "passive"))
      (node (ref "P6") (pin "1") (pinfunction "1_1") (pintype "passive"))
      (node (ref "P6") (pin "2") (pinfunction "2_2") (pintype "passive"))
      (node (ref "P6") (pin "3") (pinfunction "3_3") (pintype "passive"))
      (node (ref "R27") (pin "1") (pinfunction "1_1") (pintype "passive"))
      (node (ref "R39") (pin "1") (pinfunction "1_1") (pintype "passive"))
      (node (ref "R41") (pin "1") (pinfunction "1_1") (pintype "passive"))
      (node (ref "R51") (pin "1") (pinfunction "1_1") (pintype "passive"))
      (node (ref "R54") (pin "2") (pinfunction "2_2") (pintype "passive"))
      (node (ref "R55") (pin "2") (pinfunction "2_2") (pintype "passive"))
      (node (ref "R57") (pin "1") (pinfunction "1_1") (pintype "passive"))
      (node (ref "R61") (pin "1") (pinfunction "1_1") (pintype "passive"))
      (node (ref "TP1") (pin "1") (pinfunction "1_1") (pintype "passive"))
      (node (ref "U4") (pin "8") (pinfunction "V+_8") (pintype "passive"))
      (node (ref "U5") (pin "8") (pinfunction "VCC_8") (pintype "power_in"))
      (node (ref "U7") (pin "8") (pinfunction "VCC_8") (pintype "power_in"))
    )
    (net (code "47") (name "GND") (class "Default")
      (node (ref "BT1") (pin "2") (pinfunction "-_2") (pintype "passive"))
      (node (ref "C10") (pin "1") (pinfunction "1_1") (pintype "passive"))
      (node (ref "C11") (pin "1") (pinfunction "1_1") (pintype "passive"))
      (node (ref "C12") (pin "1") (pinfunction "1_1") (pintype "passive"))
      (node (ref "C13") (pin "1") (pinfunction "1_1") (pintype "passive"))
      (node (ref "C14") (pin "2") (pinfunction "2_2") (pintype "passive"))
      (node (ref "C15") (pin "1") (pinfunction "1_1") (pintype "passive"))
      (node (ref "C16") (pin "1") (pinfunction "1_1") (pintype "passive"))
      (node (ref "C17") (pin "2") (pinfunction "2_2") (pintype "passive"))
      (node (ref "C18") (pin "2") (pinfunction "2_2") (pintype "passive"))
      (node (ref "C19") (pin "2") (pinfunction "2_2") (pintype "passive"))
      (node (ref "C20") (pin "2") (pinfunction "2_2") (pintype "passive"))
      (node (ref "C21") (pin "1") (pinfunction "1_1") (pintype "passive"))
      (node (ref "C22") (pin "1") (pinfunction "1_1") (pintype "passive"))
      (node (ref "C23") (pin "1") (pinfunction "1_1") (pintype "passive"))
      (node (ref "C24") (pin "1") (pinfunction "1_1") (pintype "passive"))
      (node (ref "C25") (pin "1") (pinfunction "1_1") (pintype "passive"))
      (node (ref "C8") (pin "1") (pinfunction "1_1") (pintype "passive"))
      (node (ref "C9") (pin "1") (pinfunction "1_1") (pintype "passive"))
      (node (ref "P2") (pin "3") (pinfunction "3_3") (pintype "passive"))
      (node (ref "P5") (pin "3") (pinfunction "3_3") (pintype "passive"))
      (node (ref "P6") (pin "5") (pinfunction "5_5") (pintype "passive"))
      (node (ref "P7") (pin "1") (pinfunction "1_1") (pintype "passive"))
      (node (ref "R29") (pin "1") (pinfunction "1_1") (pintype "passive"))
      (node (ref "R30") (pin "1") (pinfunction "1_1") (pintype "passive"))
      (node (ref "R34") (pin "1") (pinfunction "1_1") (pintype "passive"))
      (node (ref "R35") (pin "1") (pinfunction "1_1") (pintype "passive"))
      (node (ref "R44") (pin "1") (pinfunction "1_1") (pintype "passive"))
      (node (ref "R45") (pin "1") (pinfunction "1_1") (pintype "passive"))
      (node (ref "R46") (pin "1") (pinfunction "1_1") (pintype "passive"))
      (node (ref "R47") (pin "1") (pinfunction "1_1") (pintype "passive"))
      (node (ref "S1") (pin "1") (pinfunction "1_1") (pintype "passive"))
      (node (ref "TP4") (pin "1") (pinfunction "1_1") (pintype "passive"))
      (node (ref "U3") (pin "23") (pinfunction "VSS_1_23") (pintype "passive"))
      (node (ref "U3") (pin "35") (pinfunction "VSS_2_35") (pintype "passive"))
      (node (ref "U3") (pin "47") (pinfunction "VSS_3_47") (pintype "passive"))
      (node (ref "U3") (pin "8") (pinfunction "VSSA_8") (pintype "passive"))
      (node (ref "U4") (pin "4") (pinfunction "V-_4") (pintype "passive"))
      (node (ref "U5") (pin "5") (pinfunction "GND_5") (pintype "power_in"))
      (node (ref "U6") (pin "4") (pinfunction "Vss_4") (pintype "passive"))
      (node (ref "U7") (pin "4") (pinfunction "GND_4") (pintype "power_in"))
      (node (ref "Y1") (pin "3") (pinfunction "GND_3") (pintype "passive"))
    )
    (net (code "48") (name "Net-(BT1-+)") (class "Default")
      (node (ref "BT1") (pin "1") (pinfunction "+_1") (pintype "passive"))
      (node (ref "C23") (pin "2") (pinfunction "2_2") (pintype "passive"))
      (node (ref "U7") (pin "3") (pinfunction "VBAT_3") (pintype "power_in"))
    )
    (net (code "49") (name "Net-(D10-K)") (class "Default")
      (node (ref "D10") (pin "2") (pinfunction "K_2") (pintype "passive"))
      (node (ref "R28") (pin "1") (pinfunction "1_1") (pintype "passive"))
    )
    (net (code "50") (name "Net-(P6-Pad4)") (class "Default")
      (node (ref "P6") (pin "4") (pinfunction "4_4") (pintype "passive"))
      (node (ref "R35") (pin "2") (pinfunction "2_2") (pintype "passive"))
    )
    (net (code "51") (name "Net-(U3-PD0-OSC_IN)") (class "Default")
      (node (ref "C14") (pin "1") (pinfunction "1_1") (pintype "passive"))
      (node (ref "U3") (pin "5") (pinfunction "PD0-OSC_IN_5") (pintype "passive"))
      (node (ref "X1") (pin "2") (pinfunction "2_2") (pintype "passive"))
    )
    (net (code "52") (name "Net-(U3-PD1-OSC_OUT)") (class "Default")
      (node (ref "C15") (pin "2") (pinfunction "2_2") (pintype "passive"))
      (node (ref "U3") (pin "6") (pinfunction "PD1-OSC_OUT_6") (pintype "passive"))
      (node (ref "X1") (pin "1") (pinfunction "1_1") (pintype "passive"))
    )
    (net (code "53") (name "Net-(U4-+In_A)") (class "Default")
      (node (ref "R42") (pin "2") (pinfunction "2_2") (pintype "passive"))
      (node (ref "R44") (pin "2") (pinfunction "2_2") (pintype "passive"))
      (node (ref "U4") (pin "3") (pinfunction "+In_A_3") (pintype "passive"))
    )
    (net (code "54") (name "Net-(U4-+In_B)") (class "Default")
      (node (ref "R43") (pin "1") (pinfunction "1_1") (pintype "passive"))
      (node (ref "R47") (pin "2") (pinfunction "2_2") (pintype "passive"))
      (node (ref "U4") (pin "5") (pinfunction "+In_B_5") (pintype "passive"))
    )
    (net (code "55") (name "Net-(U4--In_B)") (class "Default")
      (node (ref "R37") (pin "1") (pinfunction "1_1") (pintype "passive"))
      (node (ref "R46") (pin "2") (pinfunction "2_2") (pintype "passive"))
      (node (ref "U4") (pin "6") (pinfunction "-In_B_6") (pintype "passive"))
    )
    (net (code "56") (name "Net-(U4-–In_A)") (class "Default")
      (node (ref "R36") (pin "1") (pinfunction "1_1") (pintype "passive"))
      (node (ref "R45") (pin "2") (pinfunction "2_2") (pintype "passive"))
      (node (ref "U4") (pin "2") (pinfunction "–In_A_2") (pintype "passive"))
    )
    (net (code "57") (name "Net-(U6-~{HOLD})") (class "Default")
      (node (ref "R52") (pin "1") (pinfunction "1_1") (pintype "passive"))
      (node (ref "U6") (pin "7") (pinfunction "~{HOLD}_7") (pintype "passive"))
    )
    (net (code "58") (name "Net-(U6-~{WP})") (class "Default")
      (node (ref "R53") (pin "2") (pinfunction "2_2") (pintype "passive"))
      (node (ref "U6") (pin "3") (pinfunction "~{WP}_3") (pintype "passive"))
    )
    (net (code "59") (name "Net-(U7-X1)") (class "Default")
      (node (ref "C24") (pin "2") (pinfunction "2_2") (pintype "passive"))
      (node (ref "U7") (pin "1") (pinfunction "X1_1") (pintype "input"))
      (node (ref "Y1") (pin "2") (pinfunction "OSC2_2") (pintype "passive"))
    )
    (net (code "60") (name "Net-(U7-X2)") (class "Default")
      (node (ref "C25") (pin "2") (pinfunction "2_2") (pintype "passive"))
      (node (ref "U7") (pin "2") (pinfunction "X2_2") (pintype "input"))
      (node (ref "Y1") (pin "1") (pinfunction "OSC1_1") (pintype "passive"))
    )
    (net (code "61") (name "unconnected-(U3-PA13_{slash}JTMS{slash}SWDIO-Pad34)") (class "Default")
      (node (ref "U3") (pin "34") (pinfunction "PA13_/JTMS/SWDIO_34") (pintype "passive"))
    )
    (net (code "62") (name "unconnected-(U3-PA14_{slash}JTCK{slash}SWCLK-Pad37)") (class "Default")
      (node (ref "U3") (pin "37") (pinfunction "PA14_/JTCK/SWCLK_37") (pintype "passive"))
    )
    (net (code "63") (name "unconnected-(U3-PA15_{slash}JTDI-Pad38)") (class "Default")
      (node (ref "U3") (pin "38") (pinfunction "PA15_/JTDI_38") (pintype "passive"))
    )
    (net (code "64") (name "unconnected-(U3-PB3__{slash}JTDO-Pad39)") (class "Default")
      (node (ref "U3") (pin "39") (pinfunction "PB3__/JTDO_39") (pintype "passive"))
    )
    (net (code "65") (name "unconnected-(U3-PB8_{slash}TIM4_CH3-Pad45)") (class "Default")
      (node (ref "U3") (pin "45") (pinfunction "PB8_/TIM4_CH3_45") (pintype "passive"))
    )
    (net (code "66") (name "unconnected-(U7-SQW{slash}OUT-Pad7)") (class "Default")
      (node (ref "U7") (pin "7") (pinfunction "SQW/OUT_7") (pintype "output+no_connect"))
    )
  )
)
